# 16-ECP5_FPGA_1.net
KiCad netlist of a schematic drawn in Altium Designer
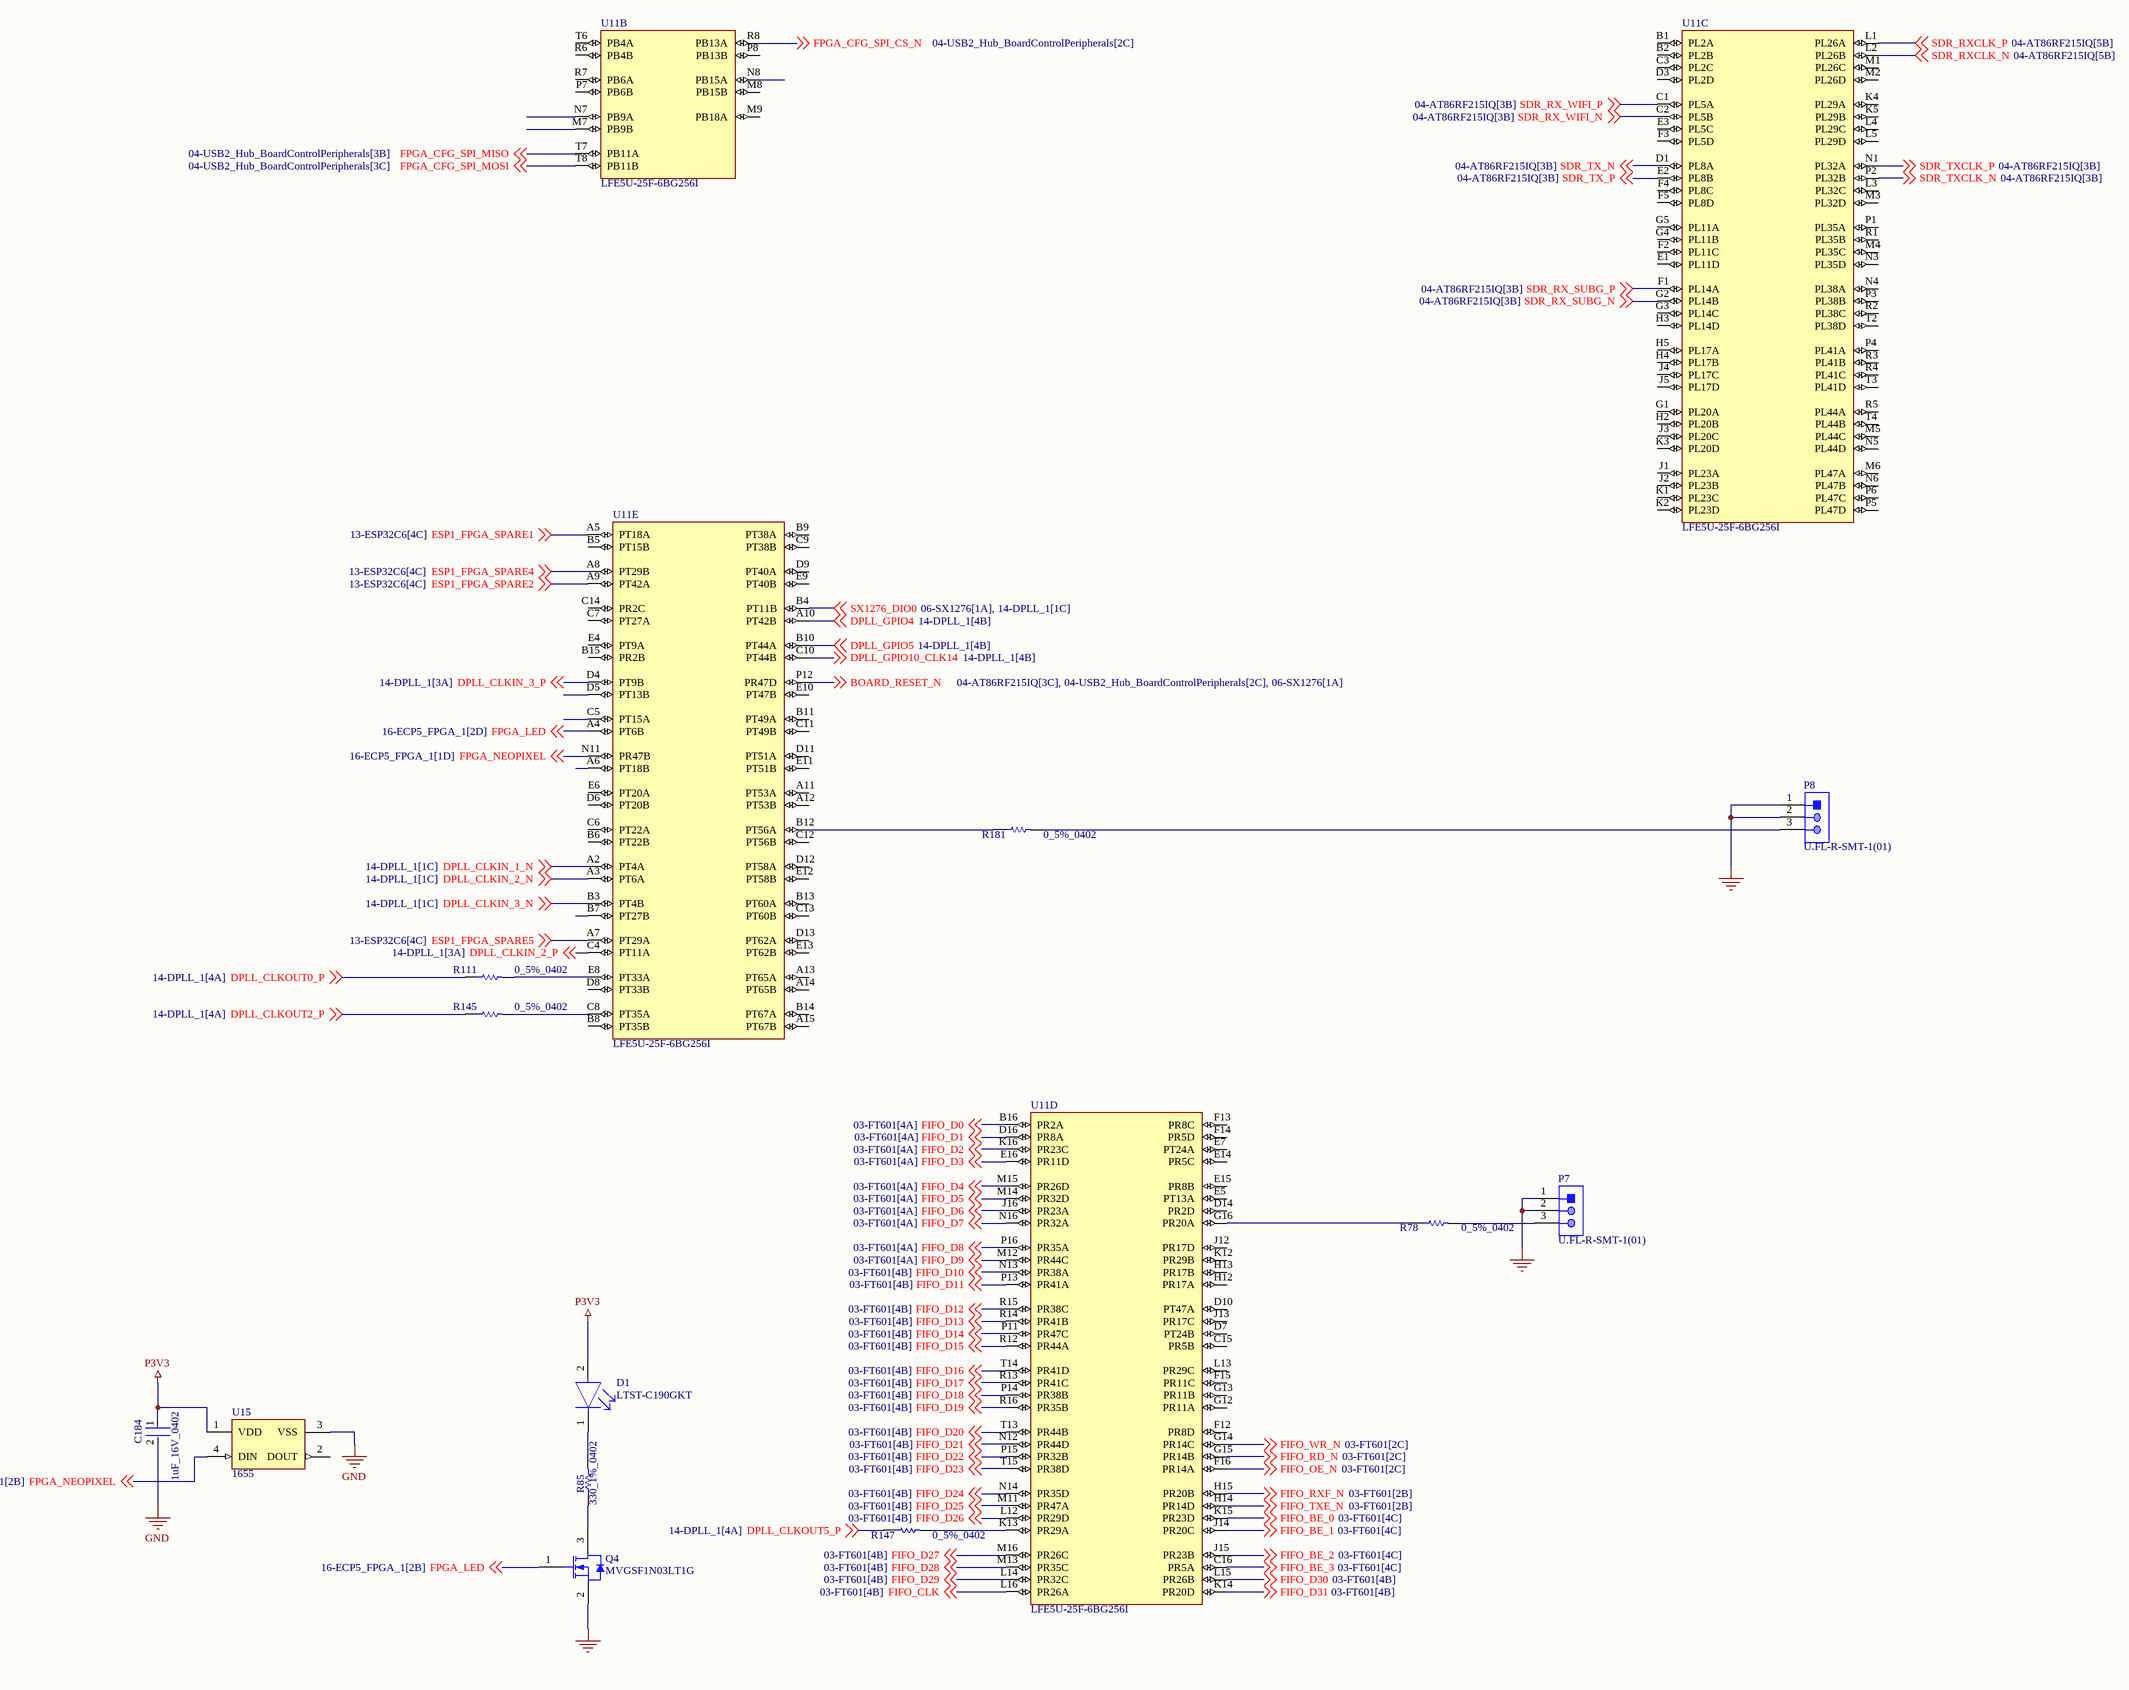
[diagram p0: 16-ECP5_FPGA_1.SchDoc]

(export (version "E")
  (design (tool "Eeschema 10.0.6"))
  (components
    (comp (ref "C184")
      (value "1uF_16V_0402")
      (footprint "FP-0402-L_1_0_0_05-W_0_5-IPC_A")
      (description "None")
      (fields (field (name "TOLERANCE") "10%"))
      (libsource (lib "Altium Content Vault") (part "b4654b650e69147ec39a6b967a45e02"))
    )
    (comp (ref "D1")
      (value "LTST-C190GKT")
      (footprint "FP-LTST-C190GKT-MFG")
      (description "LED GREEN CLEAR CHIP SMD")
      (fields (field (name "VOLTAGE") "2V"))
      (libsource (lib "Altium Content Vault") (part "8706943c75ba83719d021d2fdc84c58"))
    )
    (comp (ref "P7")
      (value "U.FL-R-SMT-1(01)")
      (footprint "HRS-U.FL-R-SMT-3_V")
      (description "Ultra Small Coaxial Connector, 6 GHz, -40 to 90 degC, 3-Pin SMD, RoHS, Bulk")
      (fields (field (name "MANUFACTURER") "Hirose Electric"))
      (libsource (lib "Altium Content Vault") (part "CN-1P-M-R3"))
    )
    (comp (ref "P8")
      (value "U.FL-R-SMT-1(01)")
      (footprint "HRS-U.FL-R-SMT-3_V")
      (description "Ultra Small Coaxial Connector, 6 GHz, -40 to 90 degC, 3-Pin SMD, RoHS, Bulk")
      (fields (field (name "MANUFACTURER") "Hirose Electric"))
      (libsource (lib "Altium Content Vault") (part "CN-1P-M-R3"))
    )
    (comp (ref "Q4")
      (value "MVGSF1N03LT1G")
      (footprint "ONSC-SOT-23-3-318-08_V")
      (description "Power MOSFET, 30 V, 2.1 A, Single N-Channel, 3-Pin SOT-23, Pb-Free, Tape and Reel")
      (fields (field (name "MANUFACTURER") "On Semiconductor"))
      (libsource (lib "Altium Content Vault") (part "ONSC-NMOS-G1S2D3-3"))
    )
    (comp (ref "R78")
      (value "0_5%_0402")
      (footprint "RESC1005X40X25NL05T10")
      (fields (field (name "MANUFACTURER") "Panasonic") (field (name "PART NUMBER") "ERJ-U020R00X"))
      (libsource (lib "Altium Content Vault") (part "RES"))
    )
    (comp (ref "R85")
      (value "330_1%_0402")
      (footprint "RESC1005X40X25NL10T10")
      (fields (field (name "MANUFACTURER") "Panasonic") (field (name "PART NUMBER") "ERA-2AED331X"))
      (libsource (lib "Altium Content Vault") (part "RES"))
    )
    (comp (ref "R111")
      (value "0_5%_0402")
      (footprint "RESC1005X40X25NL05T10")
      (fields (field (name "MANUFACTURER") "Panasonic") (field (name "PART NUMBER") "ERJ-U020R00X"))
      (libsource (lib "Altium Content Vault") (part "RES"))
    )
    (comp (ref "R145")
      (value "0_5%_0402")
      (footprint "RESC1005X40X25NL05T10")
      (fields (field (name "MANUFACTURER") "Panasonic") (field (name "PART NUMBER") "ERJ-U020R00X"))
      (libsource (lib "Altium Content Vault") (part "RES"))
    )
    (comp (ref "R147")
      (value "0_5%_0402")
      (footprint "RESC1005X40X25NL05T10")
      (fields (field (name "MANUFACTURER") "Panasonic") (field (name "PART NUMBER") "ERJ-U020R00X"))
      (libsource (lib "Altium Content Vault") (part "RES"))
    )
    (comp (ref "R181")
      (value "0_5%_0402")
      (footprint "RESC1005X40X25NL05T10")
      (fields (field (name "MANUFACTURER") "Panasonic") (field (name "PART NUMBER") "ERJ-U020R00X"))
      (libsource (lib "Altium Content Vault") (part "RES"))
    )
    (comp (ref "U11")
      (value "LFE5U-25F-6BG256I")
      (footprint "FP-LFE5U-25F-6BG256I-MFG")
      (description "IC FPGA 197 I/O 256CABGA")
      (libsource (lib "Altium Content Vault") (part "bfd34961a1b5a598594aee4faf9689d"))
    )
    (comp (ref "U15")
      (value "1655")
      (footprint "ADA-RGB-1655_V")
      (fields (field (name "MANUFACTURER") "Adafruit-Industries-LLC"))
      (libsource (lib "Altium Content Vault") (part "ADA-RGB-1655-4"))
    )
  )
  (nets
    (net (code "1") (name "BOARD_RESET_N") (class "Default")
      (node (ref "U11") (pin "P12") (pinfunction "PR47D_P12") (pintype "bidirectional"))
    )
    (net (code "2") (name "DPLL_CLKIN_1_N") (class "Default")
      (node (ref "U11") (pin "A2") (pinfunction "PT4A_A2") (pintype "bidirectional"))
    )
    (net (code "3") (name "DPLL_CLKIN_2_N") (class "Default")
      (node (ref "U11") (pin "A3") (pinfunction "PT6A_A3") (pintype "bidirectional"))
    )
    (net (code "4") (name "DPLL_CLKIN_2_P") (class "Default")
      (node (ref "U11") (pin "C4") (pinfunction "PT11A_C4") (pintype "bidirectional"))
    )
    (net (code "5") (name "DPLL_CLKIN_3_N") (class "Default")
      (node (ref "U11") (pin "B3") (pinfunction "PT4B_B3") (pintype "bidirectional"))
    )
    (net (code "6") (name "DPLL_CLKIN_3_P") (class "Default")
      (node (ref "U11") (pin "D4") (pinfunction "PT9B_D4") (pintype "bidirectional"))
    )
    (net (code "7") (name "DPLL_CLKOUT0_P") (class "Default")
      (node (ref "R111") (pin "1") (pinfunction "1_1") (pintype "passive"))
    )
    (net (code "8") (name "DPLL_CLKOUT2_P") (class "Default")
      (node (ref "R145") (pin "1") (pinfunction "1_1") (pintype "passive"))
    )
    (net (code "9") (name "DPLL_CLKOUT5_P") (class "Default")
      (node (ref "R147") (pin "1") (pinfunction "1_1") (pintype "passive"))
    )
    (net (code "10") (name "DPLL_GPIO4") (class "Default")
      (node (ref "U11") (pin "A10") (pinfunction "PT42B_A10") (pintype "bidirectional"))
    )
    (net (code "11") (name "DPLL_GPIO5") (class "Default")
      (node (ref "U11") (pin "B10") (pinfunction "PT44A_B10") (pintype "bidirectional"))
    )
    (net (code "12") (name "DPLL_GPIO10_CLK14") (class "Default")
      (node (ref "U11") (pin "C10") (pinfunction "PT44B_C10") (pintype "bidirectional"))
    )
    (net (code "13") (name "ESP1_FPGA_SPARE1") (class "Default")
      (node (ref "U11") (pin "A5") (pinfunction "PT18A_A5") (pintype "bidirectional"))
    )
    (net (code "14") (name "ESP1_FPGA_SPARE2") (class "Default")
      (node (ref "U11") (pin "A9") (pinfunction "PT42A_A9") (pintype "bidirectional"))
    )
    (net (code "15") (name "ESP1_FPGA_SPARE4") (class "Default")
      (node (ref "U11") (pin "A8") (pinfunction "PT29B_A8") (pintype "bidirectional"))
    )
    (net (code "16") (name "ESP1_FPGA_SPARE5") (class "Default")
      (node (ref "U11") (pin "A7") (pinfunction "PT29A_A7") (pintype "bidirectional"))
    )
    (net (code "17") (name "FIFO_BE_0") (class "Default")
      (node (ref "U11") (pin "K15") (pinfunction "PR23D_K15") (pintype "bidirectional"))
    )
    (net (code "18") (name "FIFO_BE_1") (class "Default")
      (node (ref "U11") (pin "J14") (pinfunction "PR20C_J14") (pintype "bidirectional"))
    )
    (net (code "19") (name "FIFO_BE_2") (class "Default")
      (node (ref "U11") (pin "J15") (pinfunction "PR23B_J15") (pintype "bidirectional"))
    )
    (net (code "20") (name "FIFO_BE_3") (class "Default")
      (node (ref "U11") (pin "C16") (pinfunction "PR5A_C16") (pintype "bidirectional"))
    )
    (net (code "21") (name "FIFO_CLK") (class "Default")
      (node (ref "U11") (pin "L16") (pinfunction "PR26A_L16") (pintype "bidirectional"))
    )
    (net (code "22") (name "FIFO_D0") (class "Default")
      (node (ref "U11") (pin "B16") (pinfunction "PR2A_B16") (pintype "bidirectional"))
    )
    (net (code "23") (name "FIFO_D1") (class "Default")
      (node (ref "U11") (pin "D16") (pinfunction "PR8A_D16") (pintype "bidirectional"))
    )
    (net (code "24") (name "FIFO_D2") (class "Default")
      (node (ref "U11") (pin "K16") (pinfunction "PR23C_K16") (pintype "bidirectional"))
    )
    (net (code "25") (name "FIFO_D3") (class "Default")
      (node (ref "U11") (pin "E16") (pinfunction "PR11D_E16") (pintype "bidirectional"))
    )
    (net (code "26") (name "FIFO_D4") (class "Default")
      (node (ref "U11") (pin "M15") (pinfunction "PR26D_M15") (pintype "bidirectional"))
    )
    (net (code "27") (name "FIFO_D5") (class "Default")
      (node (ref "U11") (pin "M14") (pinfunction "PR32D_M14") (pintype "bidirectional"))
    )
    (net (code "28") (name "FIFO_D6") (class "Default")
      (node (ref "U11") (pin "J16") (pinfunction "PR23A_J16") (pintype "bidirectional"))
    )
    (net (code "29") (name "FIFO_D7") (class "Default")
      (node (ref "U11") (pin "N16") (pinfunction "PR32A_N16") (pintype "bidirectional"))
    )
    (net (code "30") (name "FIFO_D8") (class "Default")
      (node (ref "U11") (pin "P16") (pinfunction "PR35A_P16") (pintype "bidirectional"))
    )
    (net (code "31") (name "FIFO_D9") (class "Default")
      (node (ref "U11") (pin "M12") (pinfunction "PR44C_M12") (pintype "bidirectional"))
    )
    (net (code "32") (name "FIFO_D10") (class "Default")
      (node (ref "U11") (pin "N13") (pinfunction "PR38A_N13") (pintype "bidirectional"))
    )
    (net (code "33") (name "FIFO_D11") (class "Default")
      (node (ref "U11") (pin "P13") (pinfunction "PR41A_P13") (pintype "bidirectional"))
    )
    (net (code "34") (name "FIFO_D12") (class "Default")
      (node (ref "U11") (pin "R15") (pinfunction "PR38C_R15") (pintype "bidirectional"))
    )
    (net (code "35") (name "FIFO_D13") (class "Default")
      (node (ref "U11") (pin "R14") (pinfunction "PR41B_R14") (pintype "bidirectional"))
    )
    (net (code "36") (name "FIFO_D14") (class "Default")
      (node (ref "U11") (pin "P11") (pinfunction "PR47C_P11") (pintype "bidirectional"))
    )
    (net (code "37") (name "FIFO_D15") (class "Default")
      (node (ref "U11") (pin "R12") (pinfunction "PR44A_R12") (pintype "bidirectional"))
    )
    (net (code "38") (name "FIFO_D16") (class "Default")
      (node (ref "U11") (pin "T14") (pinfunction "PR41D_T14") (pintype "bidirectional"))
    )
    (net (code "39") (name "FIFO_D17") (class "Default")
      (node (ref "U11") (pin "R13") (pinfunction "PR41C_R13") (pintype "bidirectional"))
    )
    (net (code "40") (name "FIFO_D18") (class "Default")
      (node (ref "U11") (pin "P14") (pinfunction "PR38B_P14") (pintype "bidirectional"))
    )
    (net (code "41") (name "FIFO_D19") (class "Default")
      (node (ref "U11") (pin "R16") (pinfunction "PR35B_R16") (pintype "bidirectional"))
    )
    (net (code "42") (name "FIFO_D20") (class "Default")
      (node (ref "U11") (pin "T13") (pinfunction "PR44B_T13") (pintype "bidirectional"))
    )
    (net (code "43") (name "FIFO_D21") (class "Default")
      (node (ref "U11") (pin "N12") (pinfunction "PR44D_N12") (pintype "bidirectional"))
    )
    (net (code "44") (name "FIFO_D22") (class "Default")
      (node (ref "U11") (pin "P15") (pinfunction "PR32B_P15") (pintype "bidirectional"))
    )
    (net (code "45") (name "FIFO_D23") (class "Default")
      (node (ref "U11") (pin "T15") (pinfunction "PR38D_T15") (pintype "bidirectional"))
    )
    (net (code "46") (name "FIFO_D24") (class "Default")
      (node (ref "U11") (pin "N14") (pinfunction "PR35D_N14") (pintype "bidirectional"))
    )
    (net (code "47") (name "FIFO_D25") (class "Default")
      (node (ref "U11") (pin "M11") (pinfunction "PR47A_M11") (pintype "bidirectional"))
    )
    (net (code "48") (name "FIFO_D26") (class "Default")
      (node (ref "U11") (pin "L12") (pinfunction "PR29D_L12") (pintype "bidirectional"))
    )
    (net (code "49") (name "FIFO_D27") (class "Default")
      (node (ref "U11") (pin "M16") (pinfunction "PR26C_M16") (pintype "bidirectional"))
    )
    (net (code "50") (name "FIFO_D28") (class "Default")
      (node (ref "U11") (pin "M13") (pinfunction "PR35C_M13") (pintype "bidirectional"))
    )
    (net (code "51") (name "FIFO_D29") (class "Default")
      (node (ref "U11") (pin "L14") (pinfunction "PR32C_L14") (pintype "bidirectional"))
    )
    (net (code "52") (name "FIFO_D30") (class "Default")
      (node (ref "U11") (pin "L15") (pinfunction "PR26B_L15") (pintype "bidirectional"))
    )
    (net (code "53") (name "FIFO_D31") (class "Default")
      (node (ref "U11") (pin "K14") (pinfunction "PR20D_K14") (pintype "bidirectional"))
    )
    (net (code "54") (name "FIFO_OE_N") (class "Default")
      (node (ref "U11") (pin "F16") (pinfunction "PR14A_F16") (pintype "bidirectional"))
    )
    (net (code "55") (name "FIFO_RD_N") (class "Default")
      (node (ref "U11") (pin "G15") (pinfunction "PR14B_G15") (pintype "bidirectional"))
    )
    (net (code "56") (name "FIFO_RXF_N") (class "Default")
      (node (ref "U11") (pin "H15") (pinfunction "PR20B_H15") (pintype "bidirectional"))
    )
    (net (code "57") (name "FIFO_TXE_N") (class "Default")
      (node (ref "U11") (pin "H14") (pinfunction "PR14D_H14") (pintype "bidirectional"))
    )
    (net (code "58") (name "FIFO_WR_N") (class "Default")
      (node (ref "U11") (pin "G14") (pinfunction "PR14C_G14") (pintype "bidirectional"))
    )
    (net (code "59") (name "FPGA_CFG_SPI_CS_N") (class "Default")
      (node (ref "U11") (pin "R8") (pinfunction "PB13A_R8") (pintype "bidirectional"))
    )
    (net (code "60") (name "FPGA_CFG_SPI_MISO") (class "Default")
      (node (ref "U11") (pin "T7") (pinfunction "PB11A_T7") (pintype "bidirectional"))
    )
    (net (code "61") (name "FPGA_CFG_SPI_MOSI") (class "Default")
      (node (ref "U11") (pin "T8") (pinfunction "PB11B_T8") (pintype "bidirectional"))
    )
    (net (code "62") (name "FPGA_LED") (class "Default")
      (node (ref "Q4") (pin "1") (pinfunction "G_1") (pintype "passive"))
      (node (ref "U11") (pin "A4") (pinfunction "PT6B_A4") (pintype "bidirectional"))
    )
    (net (code "63") (name "FPGA_NEOPIXEL") (class "Default")
      (node (ref "U11") (pin "N11") (pinfunction "PR47B_N11") (pintype "bidirectional"))
      (node (ref "U15") (pin "4") (pinfunction "DIN_4") (pintype "input"))
    )
    (net (code "64") (name "GND") (class "Default")
      (node (ref "C184") (pin "2") (pinfunction "2_2") (pintype "passive"))
      (node (ref "P7") (pin "1") (pinfunction "1_1") (pintype "passive"))
      (node (ref "P7") (pin "2") (pinfunction "2_2") (pintype "passive"))
      (node (ref "P8") (pin "1") (pinfunction "1_1") (pintype "passive"))
      (node (ref "P8") (pin "2") (pinfunction "2_2") (pintype "passive"))
      (node (ref "Q4") (pin "2") (pinfunction "S_2") (pintype "passive"))
      (node (ref "U15") (pin "3") (pinfunction "VSS_3") (pintype "power_in"))
    )
    (net (code "65") (name "Net-(D1-C)") (class "Default")
      (node (ref "D1") (pin "1") (pinfunction "C_1") (pintype "passive"))
      (node (ref "R85") (pin "2") (pinfunction "2_2") (pintype "passive"))
    )
    (net (code "66") (name "Net-(P7-Pad3)") (class "Default")
      (node (ref "P7") (pin "3") (pinfunction "3_3") (pintype "passive"))
      (node (ref "R78") (pin "2") (pinfunction "2_2") (pintype "passive"))
    )
    (net (code "67") (name "Net-(P8-Pad3)") (class "Default")
      (node (ref "P8") (pin "3") (pinfunction "3_3") (pintype "passive"))
      (node (ref "R181") (pin "2") (pinfunction "2_2") (pintype "passive"))
    )
    (net (code "68") (name "Net-(Q4-D)") (class "Default")
      (node (ref "Q4") (pin "3") (pinfunction "D_3") (pintype "passive"))
      (node (ref "R85") (pin "1") (pinfunction "1_1") (pintype "passive"))
    )
    (net (code "69") (name "Net-(U11D-PR20A)") (class "Default")
      (node (ref "R78") (pin "1") (pinfunction "1_1") (pintype "passive"))
      (node (ref "U11") (pin "G16") (pinfunction "PR20A_G16") (pintype "bidirectional"))
    )
    (net (code "70") (name "Net-(U11D-PR29A)") (class "Default")
      (node (ref "R147") (pin "2") (pinfunction "2_2") (pintype "passive"))
      (node (ref "U11") (pin "K13") (pinfunction "PR29A_K13") (pintype "bidirectional"))
    )
    (net (code "71") (name "Net-(U11E-PT33A)") (class "Default")
      (node (ref "R111") (pin "2") (pinfunction "2_2") (pintype "passive"))
      (node (ref "U11") (pin "E8") (pinfunction "PT33A_E8") (pintype "bidirectional"))
    )
    (net (code "72") (name "Net-(U11E-PT35A)") (class "Default")
      (node (ref "R145") (pin "2") (pinfunction "2_2") (pintype "passive"))
      (node (ref "U11") (pin "C8") (pinfunction "PT35A_C8") (pintype "bidirectional"))
    )
    (net (code "73") (name "Net-(U11E-PT56A)") (class "Default")
      (node (ref "R181") (pin "1") (pinfunction "1_1") (pintype "passive"))
      (node (ref "U11") (pin "B12") (pinfunction "PT56A_B12") (pintype "bidirectional"))
    )
    (net (code "74") (name "P3V3") (class "Default")
      (node (ref "C184") (pin "1") (pinfunction "1_1") (pintype "passive"))
      (node (ref "D1") (pin "2") (pinfunction "A_2") (pintype "passive"))
      (node (ref "U15") (pin "1") (pinfunction "VDD_1") (pintype "power_in"))
    )
    (net (code "75") (name "SDR_RXCLK_N") (class "Default")
      (node (ref "U11") (pin "L2") (pinfunction "PL26B_L2") (pintype "bidirectional"))
    )
    (net (code "76") (name "SDR_RXCLK_P") (class "Default")
      (node (ref "U11") (pin "L1") (pinfunction "PL26A_L1") (pintype "bidirectional"))
    )
    (net (code "77") (name "SDR_RX_SUBG_N") (class "Default")
      (node (ref "U11") (pin "G2") (pinfunction "PL14B_G2") (pintype "bidirectional"))
    )
    (net (code "78") (name "SDR_RX_SUBG_P") (class "Default")
      (node (ref "U11") (pin "F1") (pinfunction "PL14A_F1") (pintype "bidirectional"))
    )
    (net (code "79") (name "SDR_RX_WIFI_N") (class "Default")
      (node (ref "U11") (pin "C2") (pinfunction "PL5B_C2") (pintype "bidirectional"))
    )
    (net (code "80") (name "SDR_RX_WIFI_P") (class "Default")
      (node (ref "U11") (pin "C1") (pinfunction "PL5A_C1") (pintype "bidirectional"))
    )
    (net (code "81") (name "SDR_TXCLK_N") (class "Default")
      (node (ref "U11") (pin "P2") (pinfunction "PL32B_P2") (pintype "bidirectional"))
    )
    (net (code "82") (name "SDR_TXCLK_P") (class "Default")
      (node (ref "U11") (pin "N1") (pinfunction "PL32A_N1") (pintype "bidirectional"))
    )
    (net (code "83") (name "SDR_TX_N") (class "Default")
      (node (ref "U11") (pin "D1") (pinfunction "PL8A_D1") (pintype "bidirectional"))
    )
    (net (code "84") (name "SDR_TX_P") (class "Default")
      (node (ref "U11") (pin "E2") (pinfunction "PL8B_E2") (pintype "bidirectional"))
    )
    (net (code "85") (name "SX1276_DIO0") (class "Default")
      (node (ref "U11") (pin "B4") (pinfunction "PT11B_B4") (pintype "bidirectional"))
    )
    (net (code "86") (name "unconnected-(U11B-PB4A-PadT6)") (class "Default")
      (node (ref "U11") (pin "T6") (pinfunction "PB4A_T6") (pintype "bidirectional"))
    )
    (net (code "87") (name "unconnected-(U11B-PB4B-PadR6)") (class "Default")
      (node (ref "U11") (pin "R6") (pinfunction "PB4B_R6") (pintype "bidirectional"))
    )
    (net (code "88") (name "unconnected-(U11B-PB6A-PadR7)") (class "Default")
      (node (ref "U11") (pin "R7") (pinfunction "PB6A_R7") (pintype "bidirectional"))
    )
    (net (code "89") (name "unconnected-(U11B-PB6B-PadP7)") (class "Default")
      (node (ref "U11") (pin "P7") (pinfunction "PB6B_P7") (pintype "bidirectional"))
    )
    (net (code "90") (name "unconnected-(U11B-PB9A-PadN7)") (class "Default")
      (node (ref "U11") (pin "N7") (pinfunction "PB9A_N7") (pintype "bidirectional"))
    )
    (net (code "91") (name "unconnected-(U11B-PB9B-PadM7)") (class "Default")
      (node (ref "U11") (pin "M7") (pinfunction "PB9B_M7") (pintype "bidirectional"))
    )
    (net (code "92") (name "unconnected-(U11B-PB13B-PadP8)") (class "Default")
      (node (ref "U11") (pin "P8") (pinfunction "PB13B_P8") (pintype "bidirectional"))
    )
    (net (code "93") (name "unconnected-(U11B-PB15A-PadN8)") (class "Default")
      (node (ref "U11") (pin "N8") (pinfunction "PB15A_N8") (pintype "bidirectional"))
    )
    (net (code "94") (name "unconnected-(U11B-PB15B-PadM8)") (class "Default")
      (node (ref "U11") (pin "M8") (pinfunction "PB15B_M8") (pintype "bidirectional"))
    )
    (net (code "95") (name "unconnected-(U11B-PB18A-PadM9)") (class "Default")
      (node (ref "U11") (pin "M9") (pinfunction "PB18A_M9") (pintype "bidirectional"))
    )
    (net (code "96") (name "unconnected-(U11C-PL2A-PadB1)") (class "Default")
      (node (ref "U11") (pin "B1") (pinfunction "PL2A_B1") (pintype "bidirectional"))
    )
    (net (code "97") (name "unconnected-(U11C-PL2B-PadB2)") (class "Default")
      (node (ref "U11") (pin "B2") (pinfunction "PL2B_B2") (pintype "bidirectional"))
    )
    (net (code "98") (name "unconnected-(U11C-PL2C-PadC3)") (class "Default")
      (node (ref "U11") (pin "C3") (pinfunction "PL2C_C3") (pintype "bidirectional"))
    )
    (net (code "99") (name "unconnected-(U11C-PL2D-PadD3)") (class "Default")
      (node (ref "U11") (pin "D3") (pinfunction "PL2D_D3") (pintype "bidirectional"))
    )
    (net (code "100") (name "unconnected-(U11C-PL5C-PadE3)") (class "Default")
      (node (ref "U11") (pin "E3") (pinfunction "PL5C_E3") (pintype "bidirectional"))
    )
    (net (code "101") (name "unconnected-(U11C-PL5D-PadF3)") (class "Default")
      (node (ref "U11") (pin "F3") (pinfunction "PL5D_F3") (pintype "bidirectional"))
    )
    (net (code "102") (name "unconnected-(U11C-PL8C-PadF4)") (class "Default")
      (node (ref "U11") (pin "F4") (pinfunction "PL8C_F4") (pintype "bidirectional"))
    )
    (net (code "103") (name "unconnected-(U11C-PL8D-PadF5)") (class "Default")
      (node (ref "U11") (pin "F5") (pinfunction "PL8D_F5") (pintype "bidirectional"))
    )
    (net (code "104") (name "unconnected-(U11C-PL11A-PadG5)") (class "Default")
      (node (ref "U11") (pin "G5") (pinfunction "PL11A_G5") (pintype "bidirectional"))
    )
    (net (code "105") (name "unconnected-(U11C-PL11B-PadG4)") (class "Default")
      (node (ref "U11") (pin "G4") (pinfunction "PL11B_G4") (pintype "bidirectional"))
    )
    (net (code "106") (name "unconnected-(U11C-PL11C-PadF2)") (class "Default")
      (node (ref "U11") (pin "F2") (pinfunction "PL11C_F2") (pintype "bidirectional"))
    )
    (net (code "107") (name "unconnected-(U11C-PL11D-PadE1)") (class "Default")
      (node (ref "U11") (pin "E1") (pinfunction "PL11D_E1") (pintype "bidirectional"))
    )
    (net (code "108") (name "unconnected-(U11C-PL14C-PadG3)") (class "Default")
      (node (ref "U11") (pin "G3") (pinfunction "PL14C_G3") (pintype "bidirectional"))
    )
    (net (code "109") (name "unconnected-(U11C-PL14D-PadH3)") (class "Default")
      (node (ref "U11") (pin "H3") (pinfunction "PL14D_H3") (pintype "bidirectional"))
    )
    (net (code "110") (name "unconnected-(U11C-PL17A-PadH5)") (class "Default")
      (node (ref "U11") (pin "H5") (pinfunction "PL17A_H5") (pintype "bidirectional"))
    )
    (net (code "111") (name "unconnected-(U11C-PL17B-PadH4)") (class "Default")
      (node (ref "U11") (pin "H4") (pinfunction "PL17B_H4") (pintype "bidirectional"))
    )
    (net (code "112") (name "unconnected-(U11C-PL17C-PadJ4)") (class "Default")
      (node (ref "U11") (pin "J4") (pinfunction "PL17C_J4") (pintype "bidirectional"))
    )
    (net (code "113") (name "unconnected-(U11C-PL17D-PadJ5)") (class "Default")
      (node (ref "U11") (pin "J5") (pinfunction "PL17D_J5") (pintype "bidirectional"))
    )
    (net (code "114") (name "unconnected-(U11C-PL20A-PadG1)") (class "Default")
      (node (ref "U11") (pin "G1") (pinfunction "PL20A_G1") (pintype "bidirectional"))
    )
    (net (code "115") (name "unconnected-(U11C-PL20B-PadH2)") (class "Default")
      (node (ref "U11") (pin "H2") (pinfunction "PL20B_H2") (pintype "bidirectional"))
    )
    (net (code "116") (name "unconnected-(U11C-PL20C-PadJ3)") (class "Default")
      (node (ref "U11") (pin "J3") (pinfunction "PL20C_J3") (pintype "bidirectional"))
    )
    (net (code "117") (name "unconnected-(U11C-PL20D-PadK3)") (class "Default")
      (node (ref "U11") (pin "K3") (pinfunction "PL20D_K3") (pintype "bidirectional"))
    )
    (net (code "118") (name "unconnected-(U11C-PL23A-PadJ1)") (class "Default")
      (node (ref "U11") (pin "J1") (pinfunction "PL23A_J1") (pintype "bidirectional"))
    )
    (net (code "119") (name "unconnected-(U11C-PL23B-PadJ2)") (class "Default")
      (node (ref "U11") (pin "J2") (pinfunction "PL23B_J2") (pintype "bidirectional"))
    )
    (net (code "120") (name "unconnected-(U11C-PL23C-PadK1)") (class "Default")
      (node (ref "U11") (pin "K1") (pinfunction "PL23C_K1") (pintype "bidirectional"))
    )
    (net (code "121") (name "unconnected-(U11C-PL23D-PadK2)") (class "Default")
      (node (ref "U11") (pin "K2") (pinfunction "PL23D_K2") (pintype "bidirectional"))
    )
    (net (code "122") (name "unconnected-(U11C-PL26C-PadM1)") (class "Default")
      (node (ref "U11") (pin "M1") (pinfunction "PL26C_M1") (pintype "bidirectional"))
    )
    (net (code "123") (name "unconnected-(U11C-PL26D-PadM2)") (class "Default")
      (node (ref "U11") (pin "M2") (pinfunction "PL26D_M2") (pintype "bidirectional"))
    )
    (net (code "124") (name "unconnected-(U11C-PL29A-PadK4)") (class "Default")
      (node (ref "U11") (pin "K4") (pinfunction "PL29A_K4") (pintype "bidirectional"))
    )
    (net (code "125") (name "unconnected-(U11C-PL29B-PadK5)") (class "Default")
      (node (ref "U11") (pin "K5") (pinfunction "PL29B_K5") (pintype "bidirectional"))
    )
    (net (code "126") (name "unconnected-(U11C-PL29C-PadL4)") (class "Default")
      (node (ref "U11") (pin "L4") (pinfunction "PL29C_L4") (pintype "bidirectional"))
    )
    (net (code "127") (name "unconnected-(U11C-PL29D-PadL5)") (class "Default")
      (node (ref "U11") (pin "L5") (pinfunction "PL29D_L5") (pintype "bidirectional"))
    )
    (net (code "128") (name "unconnected-(U11C-PL32C-PadL3)") (class "Default")
      (node (ref "U11") (pin "L3") (pinfunction "PL32C_L3") (pintype "bidirectional"))
    )
    (net (code "129") (name "unconnected-(U11C-PL32D-PadM3)") (class "Default")
      (node (ref "U11") (pin "M3") (pinfunction "PL32D_M3") (pintype "bidirectional"))
    )
    (net (code "130") (name "unconnected-(U11C-PL35A-PadP1)") (class "Default")
      (node (ref "U11") (pin "P1") (pinfunction "PL35A_P1") (pintype "bidirectional"))
    )
    (net (code "131") (name "unconnected-(U11C-PL35B-PadR1)") (class "Default")
      (node (ref "U11") (pin "R1") (pinfunction "PL35B_R1") (pintype "bidirectional"))
    )
    (net (code "132") (name "unconnected-(U11C-PL35C-PadM4)") (class "Default")
      (node (ref "U11") (pin "M4") (pinfunction "PL35C_M4") (pintype "bidirectional"))
    )
    (net (code "133") (name "unconnected-(U11C-PL35D-PadN3)") (class "Default")
      (node (ref "U11") (pin "N3") (pinfunction "PL35D_N3") (pintype "bidirectional"))
    )
    (net (code "134") (name "unconnected-(U11C-PL38A-PadN4)") (class "Default")
      (node (ref "U11") (pin "N4") (pinfunction "PL38A_N4") (pintype "bidirectional"))
    )
    (net (code "135") (name "unconnected-(U11C-PL38B-PadP3)") (class "Default")
      (node (ref "U11") (pin "P3") (pinfunction "PL38B_P3") (pintype "bidirectional"))
    )
    (net (code "136") (name "unconnected-(U11C-PL38C-PadR2)") (class "Default")
      (node (ref "U11") (pin "R2") (pinfunction "PL38C_R2") (pintype "bidirectional"))
    )
    (net (code "137") (name "unconnected-(U11C-PL38D-PadT2)") (class "Default")
      (node (ref "U11") (pin "T2") (pinfunction "PL38D_T2") (pintype "bidirectional"))
    )
    (net (code "138") (name "unconnected-(U11C-PL41A-PadP4)") (class "Default")
      (node (ref "U11") (pin "P4") (pinfunction "PL41A_P4") (pintype "bidirectional"))
    )
    (net (code "139") (name "unconnected-(U11C-PL41B-PadR3)") (class "Default")
      (node (ref "U11") (pin "R3") (pinfunction "PL41B_R3") (pintype "bidirectional"))
    )
    (net (code "140") (name "unconnected-(U11C-PL41C-PadR4)") (class "Default")
      (node (ref "U11") (pin "R4") (pinfunction "PL41C_R4") (pintype "bidirectional"))
    )
    (net (code "141") (name "unconnected-(U11C-PL41D-PadT3)") (class "Default")
      (node (ref "U11") (pin "T3") (pinfunction "PL41D_T3") (pintype "bidirectional"))
    )
    (net (code "142") (name "unconnected-(U11C-PL44A-PadR5)") (class "Default")
      (node (ref "U11") (pin "R5") (pinfunction "PL44A_R5") (pintype "bidirectional"))
    )
    (net (code "143") (name "unconnected-(U11C-PL44B-PadT4)") (class "Default")
      (node (ref "U11") (pin "T4") (pinfunction "PL44B_T4") (pintype "bidirectional"))
    )
    (net (code "144") (name "unconnected-(U11C-PL44C-PadM5)") (class "Default")
      (node (ref "U11") (pin "M5") (pinfunction "PL44C_M5") (pintype "bidirectional"))
    )
    (net (code "145") (name "unconnected-(U11C-PL44D-PadN5)") (class "Default")
      (node (ref "U11") (pin "N5") (pinfunction "PL44D_N5") (pintype "bidirectional"))
    )
    (net (code "146") (name "unconnected-(U11C-PL47A-PadM6)") (class "Default")
      (node (ref "U11") (pin "M6") (pinfunction "PL47A_M6") (pintype "bidirectional"))
    )
    (net (code "147") (name "unconnected-(U11C-PL47B-PadN6)") (class "Default")
      (node (ref "U11") (pin "N6") (pinfunction "PL47B_N6") (pintype "bidirectional"))
    )
    (net (code "148") (name "unconnected-(U11C-PL47C-PadP6)") (class "Default")
      (node (ref "U11") (pin "P6") (pinfunction "PL47C_P6") (pintype "bidirectional"))
    )
    (net (code "149") (name "unconnected-(U11C-PL47D-PadP5)") (class "Default")
      (node (ref "U11") (pin "P5") (pinfunction "PL47D_P5") (pintype "bidirectional"))
    )
    (net (code "150") (name "unconnected-(U11D-PR2D-PadD14)") (class "Default")
      (node (ref "U11") (pin "D14") (pinfunction "PR2D_D14") (pintype "bidirectional"))
    )
    (net (code "151") (name "unconnected-(U11D-PR5B-PadC15)") (class "Default")
      (node (ref "U11") (pin "C15") (pinfunction "PR5B_C15") (pintype "bidirectional"))
    )
    (net (code "152") (name "unconnected-(U11D-PR5C-PadE14)") (class "Default")
      (node (ref "U11") (pin "E14") (pinfunction "PR5C_E14") (pintype "bidirectional"))
    )
    (net (code "153") (name "unconnected-(U11D-PR5D-PadF14)") (class "Default")
      (node (ref "U11") (pin "F14") (pinfunction "PR5D_F14") (pintype "bidirectional"))
    )
    (net (code "154") (name "unconnected-(U11D-PR8B-PadE15)") (class "Default")
      (node (ref "U11") (pin "E15") (pinfunction "PR8B_E15") (pintype "bidirectional"))
    )
    (net (code "155") (name "unconnected-(U11D-PR8C-PadF13)") (class "Default")
      (node (ref "U11") (pin "F13") (pinfunction "PR8C_F13") (pintype "bidirectional"))
    )
    (net (code "156") (name "unconnected-(U11D-PR8D-PadF12)") (class "Default")
      (node (ref "U11") (pin "F12") (pinfunction "PR8D_F12") (pintype "bidirectional"))
    )
    (net (code "157") (name "unconnected-(U11D-PR11A-PadG12)") (class "Default")
      (node (ref "U11") (pin "G12") (pinfunction "PR11A_G12") (pintype "bidirectional"))
    )
    (net (code "158") (name "unconnected-(U11D-PR11B-PadG13)") (class "Default")
      (node (ref "U11") (pin "G13") (pinfunction "PR11B_G13") (pintype "bidirectional"))
    )
    (net (code "159") (name "unconnected-(U11D-PR11C-PadF15)") (class "Default")
      (node (ref "U11") (pin "F15") (pinfunction "PR11C_F15") (pintype "bidirectional"))
    )
    (net (code "160") (name "unconnected-(U11D-PR17A-PadH12)") (class "Default")
      (node (ref "U11") (pin "H12") (pinfunction "PR17A_H12") (pintype "bidirectional"))
    )
    (net (code "161") (name "unconnected-(U11D-PR17B-PadH13)") (class "Default")
      (node (ref "U11") (pin "H13") (pinfunction "PR17B_H13") (pintype "bidirectional"))
    )
    (net (code "162") (name "unconnected-(U11D-PR17C-PadJ13)") (class "Default")
      (node (ref "U11") (pin "J13") (pinfunction "PR17C_J13") (pintype "bidirectional"))
    )
    (net (code "163") (name "unconnected-(U11D-PR17D-PadJ12)") (class "Default")
      (node (ref "U11") (pin "J12") (pinfunction "PR17D_J12") (pintype "bidirectional"))
    )
    (net (code "164") (name "unconnected-(U11D-PR29B-PadK12)") (class "Default")
      (node (ref "U11") (pin "K12") (pinfunction "PR29B_K12") (pintype "bidirectional"))
    )
    (net (code "165") (name "unconnected-(U11D-PR29C-PadL13)") (class "Default")
      (node (ref "U11") (pin "L13") (pinfunction "PR29C_L13") (pintype "bidirectional"))
    )
    (net (code "166") (name "unconnected-(U11D-PT13A-PadE5)") (class "Default")
      (node (ref "U11") (pin "E5") (pinfunction "PT13A_E5") (pintype "bidirectional"))
    )
    (net (code "167") (name "unconnected-(U11D-PT24A-PadE7)") (class "Default")
      (node (ref "U11") (pin "E7") (pinfunction "PT24A_E7") (pintype "bidirectional"))
    )
    (net (code "168") (name "unconnected-(U11D-PT24B-PadD7)") (class "Default")
      (node (ref "U11") (pin "D7") (pinfunction "PT24B_D7") (pintype "bidirectional"))
    )
    (net (code "169") (name "unconnected-(U11D-PT47A-PadD10)") (class "Default")
      (node (ref "U11") (pin "D10") (pinfunction "PT47A_D10") (pintype "bidirectional"))
    )
    (net (code "170") (name "unconnected-(U11E-PR2B-PadB15)") (class "Default")
      (node (ref "U11") (pin "B15") (pinfunction "PR2B_B15") (pintype "bidirectional"))
    )
    (net (code "171") (name "unconnected-(U11E-PR2C-PadC14)") (class "Default")
      (node (ref "U11") (pin "C14") (pinfunction "PR2C_C14") (pintype "bidirectional"))
    )
    (net (code "172") (name "unconnected-(U11E-PT9A-PadE4)") (class "Default")
      (node (ref "U11") (pin "E4") (pinfunction "PT9A_E4") (pintype "bidirectional"))
    )
    (net (code "173") (name "unconnected-(U11E-PT13B-PadD5)") (class "Default")
      (node (ref "U11") (pin "D5") (pinfunction "PT13B_D5") (pintype "bidirectional"))
    )
    (net (code "174") (name "unconnected-(U11E-PT15A-PadC5)") (class "Default")
      (node (ref "U11") (pin "C5") (pinfunction "PT15A_C5") (pintype "bidirectional"))
    )
    (net (code "175") (name "unconnected-(U11E-PT15B-PadB5)") (class "Default")
      (node (ref "U11") (pin "B5") (pinfunction "PT15B_B5") (pintype "bidirectional"))
    )
    (net (code "176") (name "unconnected-(U11E-PT18B-PadA6)") (class "Default")
      (node (ref "U11") (pin "A6") (pinfunction "PT18B_A6") (pintype "bidirectional"))
    )
    (net (code "177") (name "unconnected-(U11E-PT20A-PadE6)") (class "Default")
      (node (ref "U11") (pin "E6") (pinfunction "PT20A_E6") (pintype "bidirectional"))
    )
    (net (code "178") (name "unconnected-(U11E-PT20B-PadD6)") (class "Default")
      (node (ref "U11") (pin "D6") (pinfunction "PT20B_D6") (pintype "bidirectional"))
    )
    (net (code "179") (name "unconnected-(U11E-PT22A-PadC6)") (class "Default")
      (node (ref "U11") (pin "C6") (pinfunction "PT22A_C6") (pintype "bidirectional"))
    )
    (net (code "180") (name "unconnected-(U11E-PT22B-PadB6)") (class "Default")
      (node (ref "U11") (pin "B6") (pinfunction "PT22B_B6") (pintype "bidirectional"))
    )
    (net (code "181") (name "unconnected-(U11E-PT27A-PadC7)") (class "Default")
      (node (ref "U11") (pin "C7") (pinfunction "PT27A_C7") (pintype "bidirectional"))
    )
    (net (code "182") (name "unconnected-(U11E-PT27B-PadB7)") (class "Default")
      (node (ref "U11") (pin "B7") (pinfunction "PT27B_B7") (pintype "bidirectional"))
    )
    (net (code "183") (name "unconnected-(U11E-PT33B-PadD8)") (class "Default")
      (node (ref "U11") (pin "D8") (pinfunction "PT33B_D8") (pintype "bidirectional"))
    )
    (net (code "184") (name "unconnected-(U11E-PT35B-PadB8)") (class "Default")
      (node (ref "U11") (pin "B8") (pinfunction "PT35B_B8") (pintype "bidirectional"))
    )
    (net (code "185") (name "unconnected-(U11E-PT38A-PadB9)") (class "Default")
      (node (ref "U11") (pin "B9") (pinfunction "PT38A_B9") (pintype "bidirectional"))
    )
    (net (code "186") (name "unconnected-(U11E-PT38B-PadC9)") (class "Default")
      (node (ref "U11") (pin "C9") (pinfunction "PT38B_C9") (pintype "bidirectional"))
    )
    (net (code "187") (name "unconnected-(U11E-PT40A-PadD9)") (class "Default")
      (node (ref "U11") (pin "D9") (pinfunction "PT40A_D9") (pintype "bidirectional"))
    )
    (net (code "188") (name "unconnected-(U11E-PT40B-PadE9)") (class "Default")
      (node (ref "U11") (pin "E9") (pinfunction "PT40B_E9") (pintype "bidirectional"))
    )
    (net (code "189") (name "unconnected-(U11E-PT47B-PadE10)") (class "Default")
      (node (ref "U11") (pin "E10") (pinfunction "PT47B_E10") (pintype "bidirectional"))
    )
    (net (code "190") (name "unconnected-(U11E-PT49A-PadB11)") (class "Default")
      (node (ref "U11") (pin "B11") (pinfunction "PT49A_B11") (pintype "bidirectional"))
    )
    (net (code "191") (name "unconnected-(U11E-PT49B-PadC11)") (class "Default")
      (node (ref "U11") (pin "C11") (pinfunction "PT49B_C11") (pintype "bidirectional"))
    )
    (net (code "192") (name "unconnected-(U11E-PT51A-PadD11)") (class "Default")
      (node (ref "U11") (pin "D11") (pinfunction "PT51A_D11") (pintype "bidirectional"))
    )
    (net (code "193") (name "unconnected-(U11E-PT51B-PadE11)") (class "Default")
      (node (ref "U11") (pin "E11") (pinfunction "PT51B_E11") (pintype "bidirectional"))
    )
    (net (code "194") (name "unconnected-(U11E-PT53A-PadA11)") (class "Default")
      (node (ref "U11") (pin "A11") (pinfunction "PT53A_A11") (pintype "bidirectional"))
    )
    (net (code "195") (name "unconnected-(U11E-PT53B-PadA12)") (class "Default")
      (node (ref "U11") (pin "A12") (pinfunction "PT53B_A12") (pintype "bidirectional"))
    )
    (net (code "196") (name "unconnected-(U11E-PT56B-PadC12)") (class "Default")
      (node (ref "U11") (pin "C12") (pinfunction "PT56B_C12") (pintype "bidirectional"))
    )
    (net (code "197") (name "unconnected-(U11E-PT58A-PadD12)") (class "Default")
      (node (ref "U11") (pin "D12") (pinfunction "PT58A_D12") (pintype "bidirectional"))
    )
    (net (code "198") (name "unconnected-(U11E-PT58B-PadE12)") (class "Default")
      (node (ref "U11") (pin "E12") (pinfunction "PT58B_E12") (pintype "bidirectional"))
    )
    (net (code "199") (name "unconnected-(U11E-PT60A-PadB13)") (class "Default")
      (node (ref "U11") (pin "B13") (pinfunction "PT60A_B13") (pintype "bidirectional"))
    )
    (net (code "200") (name "unconnected-(U11E-PT60B-PadC13)") (class "Default")
      (node (ref "U11") (pin "C13") (pinfunction "PT60B_C13") (pintype "bidirectional"))
    )
    (net (code "201") (name "unconnected-(U11E-PT62A-PadD13)") (class "Default")
      (node (ref "U11") (pin "D13") (pinfunction "PT62A_D13") (pintype "bidirectional"))
    )
    (net (code "202") (name "unconnected-(U11E-PT62B-PadE13)") (class "Default")
      (node (ref "U11") (pin "E13") (pinfunction "PT62B_E13") (pintype "bidirectional"))
    )
    (net (code "203") (name "unconnected-(U11E-PT65A-PadA13)") (class "Default")
      (node (ref "U11") (pin "A13") (pinfunction "PT65A_A13") (pintype "bidirectional"))
    )
    (net (code "204") (name "unconnected-(U11E-PT65B-PadA14)") (class "Default")
      (node (ref "U11") (pin "A14") (pinfunction "PT65B_A14") (pintype "bidirectional"))
    )
    (net (code "205") (name "unconnected-(U11E-PT67A-PadB14)") (class "Default")
      (node (ref "U11") (pin "B14") (pinfunction "PT67A_B14") (pintype "bidirectional"))
    )
    (net (code "206") (name "unconnected-(U11E-PT67B-PadA15)") (class "Default")
      (node (ref "U11") (pin "A15") (pinfunction "PT67B_A15") (pintype "bidirectional"))
    )
    (net (code "207") (name "unconnected-(U15-DOUT-Pad2)") (class "Default")
      (node (ref "U15") (pin "2") (pinfunction "DOUT_2") (pintype "output"))
    )
  )
)
